# buttonboard-center.net
KiCad netlist of a schematic drawn in EAGLE
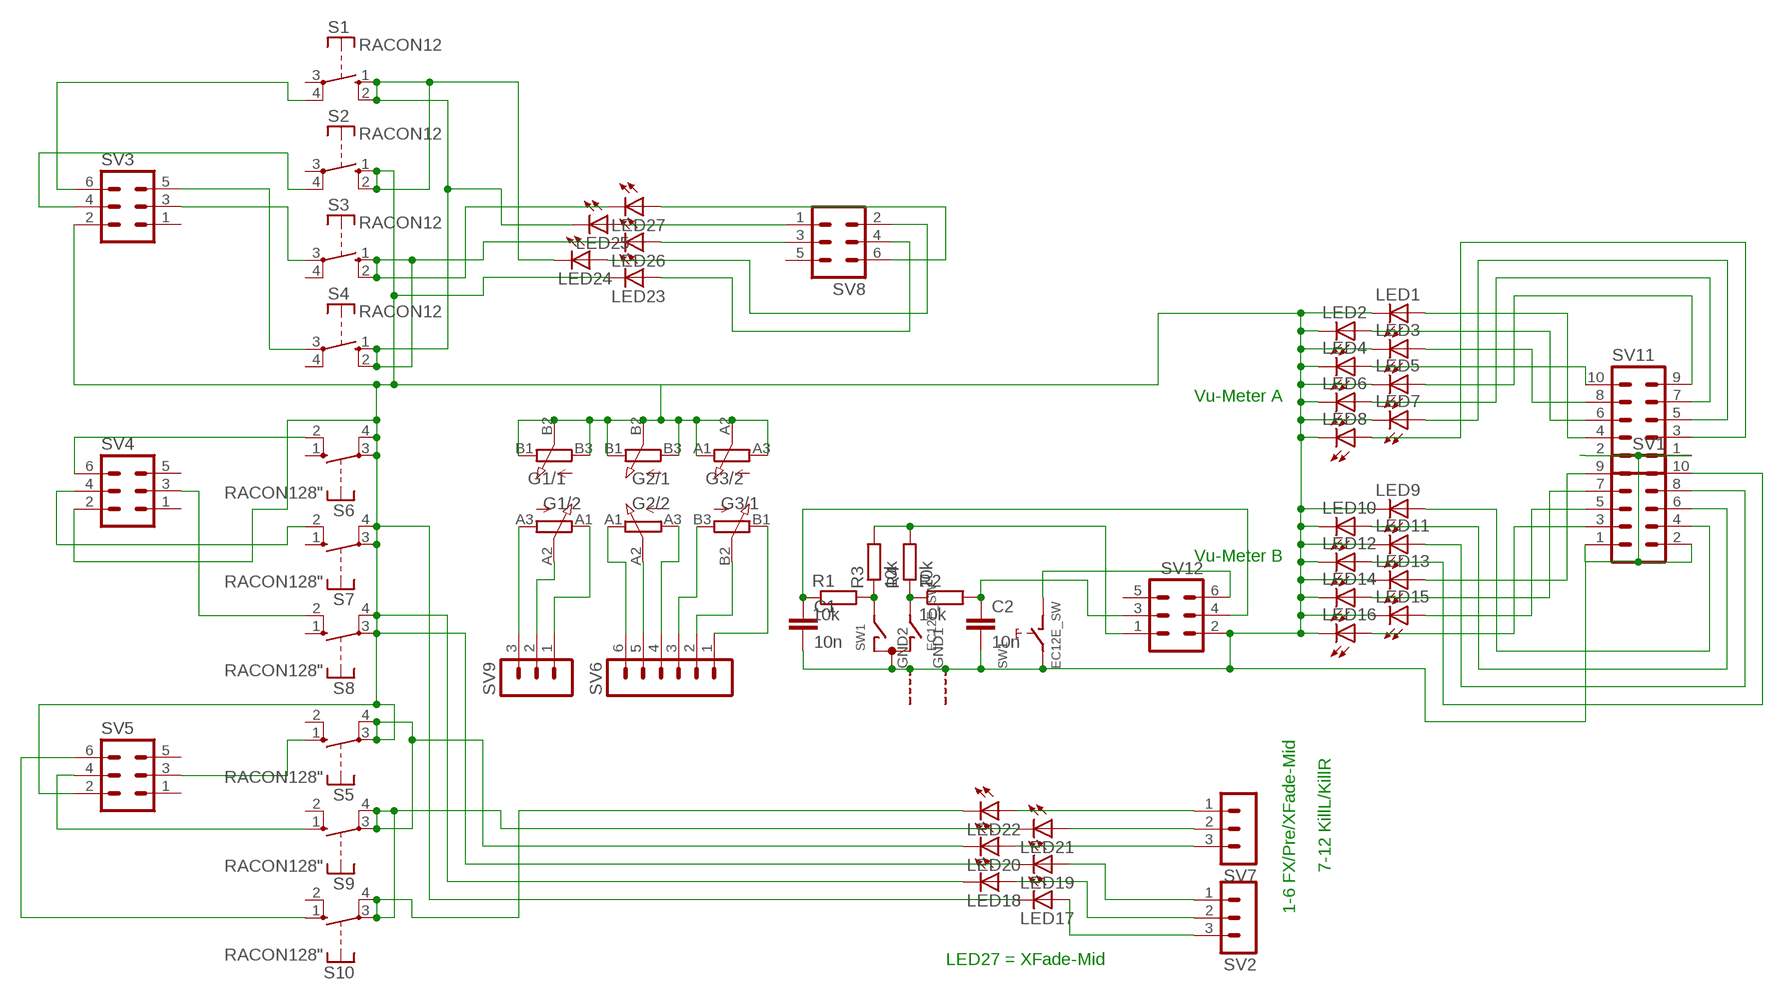
[diagram p0: schematic, sheet 1]

(export (version "E")
  (design (tool "Eeschema 10.0.6"))
  (components
    (comp (ref "C1")
      (value "10n")
      (footprint "eagle-import:C025-025X050")
      (libsource (lib "eagle-import") (part "C-EU025-025X050"))
    )
    (comp (ref "C2")
      (value "10n")
      (footprint "eagle-import:C025-025X050")
      (libsource (lib "eagle-import") (part "C-EU025-025X050"))
    )
    (comp (ref "G1")
      (value "RS60112RS")
      (footprint "eagle-import:RS60112")
      (libsource (lib "eagle-import") (part "RS60112RS"))
    )
    (comp (ref "G2")
      (value "RS60112RS")
      (footprint "eagle-import:RS60112")
      (libsource (lib "eagle-import") (part "RS60112RS"))
    )
    (comp (ref "G3")
      (value "RS60112RS")
      (footprint "eagle-import:RS60112")
      (libsource (lib "eagle-import") (part "RS60112RS"))
    )
    (comp (ref "LED1")
      (value "LED3MM")
      (footprint "eagle-import:LED3MM")
      (libsource (lib "eagle-import") (part "LED3MM"))
    )
    (comp (ref "LED2")
      (value "LED3MM")
      (footprint "eagle-import:LED3MM")
      (libsource (lib "eagle-import") (part "LED3MM"))
    )
    (comp (ref "LED3")
      (value "LED3MM")
      (footprint "eagle-import:LED3MM")
      (libsource (lib "eagle-import") (part "LED3MM"))
    )
    (comp (ref "LED4")
      (value "LED3MM")
      (footprint "eagle-import:LED3MM")
      (libsource (lib "eagle-import") (part "LED3MM"))
    )
    (comp (ref "LED5")
      (value "LED3MM")
      (footprint "eagle-import:LED3MM")
      (libsource (lib "eagle-import") (part "LED3MM"))
    )
    (comp (ref "LED6")
      (value "LED3MM")
      (footprint "eagle-import:LED3MM")
      (libsource (lib "eagle-import") (part "LED3MM"))
    )
    (comp (ref "LED7")
      (value "LED3MM")
      (footprint "eagle-import:LED3MM")
      (libsource (lib "eagle-import") (part "LED3MM"))
    )
    (comp (ref "LED8")
      (value "LED3MM")
      (footprint "eagle-import:LED3MM")
      (libsource (lib "eagle-import") (part "LED3MM"))
    )
    (comp (ref "LED9")
      (value "LED3MM")
      (footprint "eagle-import:LED3MM")
      (libsource (lib "eagle-import") (part "LED3MM"))
    )
    (comp (ref "LED10")
      (value "LED3MM")
      (footprint "eagle-import:LED3MM")
      (libsource (lib "eagle-import") (part "LED3MM"))
    )
    (comp (ref "LED11")
      (value "LED3MM")
      (footprint "eagle-import:LED3MM")
      (libsource (lib "eagle-import") (part "LED3MM"))
    )
    (comp (ref "LED12")
      (value "LED3MM")
      (footprint "eagle-import:LED3MM")
      (libsource (lib "eagle-import") (part "LED3MM"))
    )
    (comp (ref "LED13")
      (value "LED3MM")
      (footprint "eagle-import:LED3MM")
      (libsource (lib "eagle-import") (part "LED3MM"))
    )
    (comp (ref "LED14")
      (value "LED3MM")
      (footprint "eagle-import:LED3MM")
      (libsource (lib "eagle-import") (part "LED3MM"))
    )
    (comp (ref "LED15")
      (value "LED3MM")
      (footprint "eagle-import:LED3MM")
      (libsource (lib "eagle-import") (part "LED3MM"))
    )
    (comp (ref "LED16")
      (value "LED3MM")
      (footprint "eagle-import:LED3MM")
      (libsource (lib "eagle-import") (part "LED3MM"))
    )
    (comp (ref "LED17")
      (value "LED3MM")
      (footprint "eagle-import:LED3MM")
      (libsource (lib "eagle-import") (part "LED3MM"))
    )
    (comp (ref "LED18")
      (value "LED3MM")
      (footprint "eagle-import:LED3MM")
      (libsource (lib "eagle-import") (part "LED3MM"))
    )
    (comp (ref "LED19")
      (value "LED3MM")
      (footprint "eagle-import:LED3MM")
      (libsource (lib "eagle-import") (part "LED3MM"))
    )
    (comp (ref "LED20")
      (value "LED3MM")
      (footprint "eagle-import:LED3MM")
      (libsource (lib "eagle-import") (part "LED3MM"))
    )
    (comp (ref "LED21")
      (value "LED3MM")
      (footprint "eagle-import:LED3MM")
      (libsource (lib "eagle-import") (part "LED3MM"))
    )
    (comp (ref "LED22")
      (value "LED3MM")
      (footprint "eagle-import:LED3MM")
      (libsource (lib "eagle-import") (part "LED3MM"))
    )
    (comp (ref "LED23")
      (value "LED3MM")
      (footprint "eagle-import:LED3MM")
      (libsource (lib "eagle-import") (part "LED3MM"))
    )
    (comp (ref "LED24")
      (value "LED3MM")
      (footprint "eagle-import:LED3MM")
      (libsource (lib "eagle-import") (part "LED3MM"))
    )
    (comp (ref "LED25")
      (value "LED3MM")
      (footprint "eagle-import:LED3MM")
      (libsource (lib "eagle-import") (part "LED3MM"))
    )
    (comp (ref "LED26")
      (value "LED3MM")
      (footprint "eagle-import:LED3MM")
      (libsource (lib "eagle-import") (part "LED3MM"))
    )
    (comp (ref "LED27")
      (value "LED3MM")
      (footprint "eagle-import:LED3MM")
      (libsource (lib "eagle-import") (part "LED3MM"))
    )
    (comp (ref "R1")
      (value "10k")
      (footprint "eagle-import:0207_7")
      (libsource (lib "eagle-import") (part "R-EU_0207/7"))
    )
    (comp (ref "R2")
      (value "10k")
      (footprint "eagle-import:0207_7")
      (libsource (lib "eagle-import") (part "R-EU_0207/7"))
    )
    (comp (ref "R3")
      (value "10k")
      (footprint "eagle-import:0207_7")
      (libsource (lib "eagle-import") (part "R-EU_0207/7"))
    )
    (comp (ref "R4")
      (value "10k")
      (footprint "eagle-import:0207_7")
      (libsource (lib "eagle-import") (part "R-EU_0207/7"))
    )
    (comp (ref "S1")
      (value "RACON12")
      (footprint "eagle-import:RACON12")
      (libsource (lib "eagle-import") (part "RACON12"))
    )
    (comp (ref "S2")
      (value "RACON12")
      (footprint "eagle-import:RACON12")
      (libsource (lib "eagle-import") (part "RACON12"))
    )
    (comp (ref "S3")
      (value "RACON12")
      (footprint "eagle-import:RACON12")
      (libsource (lib "eagle-import") (part "RACON12"))
    )
    (comp (ref "S4")
      (value "RACON12")
      (footprint "eagle-import:RACON12")
      (libsource (lib "eagle-import") (part "RACON12"))
    )
    (comp (ref "S5")
      (value "RACON128\"")
      (footprint "eagle-import:RACON8")
      (libsource (lib "eagle-import") (part "RACON128{dblquote}"))
    )
    (comp (ref "S6")
      (value "RACON128\"")
      (footprint "eagle-import:RACON8")
      (libsource (lib "eagle-import") (part "RACON128{dblquote}"))
    )
    (comp (ref "S7")
      (value "RACON128\"")
      (footprint "eagle-import:RACON8")
      (libsource (lib "eagle-import") (part "RACON128{dblquote}"))
    )
    (comp (ref "S8")
      (value "RACON128\"")
      (footprint "eagle-import:RACON8")
      (libsource (lib "eagle-import") (part "RACON128{dblquote}"))
    )
    (comp (ref "S9")
      (value "RACON128\"")
      (footprint "eagle-import:RACON8")
      (libsource (lib "eagle-import") (part "RACON128{dblquote}"))
    )
    (comp (ref "S10")
      (value "RACON128\"")
      (footprint "eagle-import:RACON8")
      (libsource (lib "eagle-import") (part "RACON128{dblquote}"))
    )
    (comp (ref "SV1")
      (value "MA05-2")
      (footprint "eagle-import:MA05-2")
      (fields (field (name "OC_FARNELL") "unknown") (field (name "OC_NEWARK") "unknown"))
      (libsource (lib "eagle-import") (part "MA05-2"))
    )
    (comp (ref "SV2")
      (value "MA03-1")
      (footprint "eagle-import:MA03-1")
      (libsource (lib "eagle-import") (part "MA03-1"))
    )
    (comp (ref "SV3")
      (value "MA03-2")
      (footprint "eagle-import:MA03-2")
      (libsource (lib "eagle-import") (part "MA03-2"))
    )
    (comp (ref "SV4")
      (value "MA03-2")
      (footprint "eagle-import:MA03-2")
      (libsource (lib "eagle-import") (part "MA03-2"))
    )
    (comp (ref "SV5")
      (value "MA03-2")
      (footprint "eagle-import:MA03-2")
      (libsource (lib "eagle-import") (part "MA03-2"))
    )
    (comp (ref "SV6")
      (value "MA06-1")
      (footprint "eagle-import:MA06-1")
      (libsource (lib "eagle-import") (part "MA06-1"))
    )
    (comp (ref "SV7")
      (value "MA03-1")
      (footprint "eagle-import:MA03-1")
      (libsource (lib "eagle-import") (part "MA03-1"))
    )
    (comp (ref "SV8")
      (value "MA03-2")
      (footprint "eagle-import:MA03-2")
      (libsource (lib "eagle-import") (part "MA03-2"))
    )
    (comp (ref "SV9")
      (value "MA03-1")
      (footprint "eagle-import:MA03-1")
      (libsource (lib "eagle-import") (part "MA03-1"))
    )
    (comp (ref "SV11")
      (value "MA05-2")
      (footprint "eagle-import:MA05-2")
      (libsource (lib "eagle-import") (part "MA05-2"))
    )
    (comp (ref "SV12")
      (value "MA03-2")
      (footprint "eagle-import:MA03-2")
      (fields (field (name "OC_FARNELL") "unknown") (field (name "OC_NEWARK") "unknown"))
      (libsource (lib "eagle-import") (part "MA03-2"))
    )
    (comp (ref "SW1")
      (value "EC12E_SW")
      (footprint "eagle-import:ALPS_EC12E_SW")
      (fields (field (name "MPN") "EC12E2424407"))
      (libsource (lib "eagle-import") (part "EC12E_SW"))
    )
  )
  (nets
    (net (code "1") (name "Net-(C1-Pad1)") (class "Default")
      (node (ref "C1") (pin "1") (pinfunction "1_1") (pintype "passive"))
      (node (ref "R1") (pin "1") (pinfunction "1_1") (pintype "passive"))
      (node (ref "SV12") (pin "4") (pinfunction "4_4") (pintype "passive"))
    )
    (net (code "2") (name "Net-(C2-Pad1)") (class "Default")
      (node (ref "C2") (pin "1") (pinfunction "1_1") (pintype "passive"))
      (node (ref "R2") (pin "2") (pinfunction "2_2") (pintype "passive"))
      (node (ref "SV12") (pin "3") (pinfunction "3_3") (pintype "passive"))
    )
    (net (code "3") (name "Net-(G1A-A)") (class "Default")
      (node (ref "G1") (pin "A3") (pinfunction "A_A3") (pintype "passive"))
      (node (ref "SV9") (pin "3") (pinfunction "3_3") (pintype "passive"))
    )
    (net (code "4") (name "Net-(G1A-E)") (class "Default")
      (node (ref "G1") (pin "A1") (pinfunction "E_A1") (pintype "passive"))
      (node (ref "SV9") (pin "1") (pinfunction "1_1") (pintype "passive"))
    )
    (net (code "5") (name "Net-(G1A-S)") (class "Default")
      (node (ref "G1") (pin "A2") (pinfunction "S_A2") (pintype "passive"))
      (node (ref "SV9") (pin "2") (pinfunction "2_2") (pintype "passive"))
    )
    (net (code "6") (name "Net-(G1B-A)") (class "Default")
      (node (ref "C1") (pin "2") (pinfunction "2_2") (pintype "passive"))
      (node (ref "C2") (pin "2") (pinfunction "2_2") (pintype "passive"))
      (node (ref "G1") (pin "B1") (pinfunction "E_B1") (pintype "passive"))
      (node (ref "G1") (pin "B2") (pinfunction "S_B2") (pintype "passive"))
      (node (ref "G1") (pin "B3") (pinfunction "A_B3") (pintype "passive"))
      (node (ref "G2") (pin "B1") (pinfunction "E_B1") (pintype "passive"))
      (node (ref "G2") (pin "B2") (pinfunction "S_B2") (pintype "passive"))
      (node (ref "G2") (pin "B3") (pinfunction "A_B3") (pintype "passive"))
      (node (ref "G3") (pin "A1") (pinfunction "E_A1") (pintype "passive"))
      (node (ref "G3") (pin "A2") (pinfunction "S_A2") (pintype "passive"))
      (node (ref "G3") (pin "A3") (pinfunction "A_A3") (pintype "passive"))
      (node (ref "LED1") (pin "K") (pinfunction "C_K") (pintype "passive"))
      (node (ref "LED10") (pin "K") (pinfunction "C_K") (pintype "passive"))
      (node (ref "LED11") (pin "K") (pinfunction "C_K") (pintype "passive"))
      (node (ref "LED12") (pin "K") (pinfunction "C_K") (pintype "passive"))
      (node (ref "LED13") (pin "K") (pinfunction "C_K") (pintype "passive"))
      (node (ref "LED14") (pin "K") (pinfunction "C_K") (pintype "passive"))
      (node (ref "LED15") (pin "K") (pinfunction "C_K") (pintype "passive"))
      (node (ref "LED16") (pin "K") (pinfunction "C_K") (pintype "passive"))
      (node (ref "LED17") (pin "K") (pinfunction "C_K") (pintype "passive"))
      (node (ref "LED18") (pin "K") (pinfunction "C_K") (pintype "passive"))
      (node (ref "LED19") (pin "K") (pinfunction "C_K") (pintype "passive"))
      (node (ref "LED2") (pin "K") (pinfunction "C_K") (pintype "passive"))
      (node (ref "LED20") (pin "K") (pinfunction "C_K") (pintype "passive"))
      (node (ref "LED21") (pin "K") (pinfunction "C_K") (pintype "passive"))
      (node (ref "LED22") (pin "K") (pinfunction "C_K") (pintype "passive"))
      (node (ref "LED23") (pin "K") (pinfunction "C_K") (pintype "passive"))
      (node (ref "LED24") (pin "K") (pinfunction "C_K") (pintype "passive"))
      (node (ref "LED25") (pin "K") (pinfunction "C_K") (pintype "passive"))
      (node (ref "LED26") (pin "K") (pinfunction "C_K") (pintype "passive"))
      (node (ref "LED27") (pin "K") (pinfunction "C_K") (pintype "passive"))
      (node (ref "LED3") (pin "K") (pinfunction "C_K") (pintype "passive"))
      (node (ref "LED4") (pin "K") (pinfunction "C_K") (pintype "passive"))
      (node (ref "LED5") (pin "K") (pinfunction "C_K") (pintype "passive"))
      (node (ref "LED6") (pin "K") (pinfunction "C_K") (pintype "passive"))
      (node (ref "LED7") (pin "K") (pinfunction "C_K") (pintype "passive"))
      (node (ref "LED8") (pin "K") (pinfunction "C_K") (pintype "passive"))
      (node (ref "LED9") (pin "K") (pinfunction "C_K") (pintype "passive"))
      (node (ref "S1") (pin "1") (pinfunction "S_1") (pintype "passive"))
      (node (ref "S1") (pin "2") (pinfunction "S_2") (pintype "passive"))
      (node (ref "S10") (pin "3") (pinfunction "P_3") (pintype "passive"))
      (node (ref "S10") (pin "4") (pinfunction "P_4") (pintype "passive"))
      (node (ref "S2") (pin "1") (pinfunction "S_1") (pintype "passive"))
      (node (ref "S2") (pin "2") (pinfunction "S_2") (pintype "passive"))
      (node (ref "S3") (pin "1") (pinfunction "S_1") (pintype "passive"))
      (node (ref "S3") (pin "2") (pinfunction "S_2") (pintype "passive"))
      (node (ref "S4") (pin "1") (pinfunction "S_1") (pintype "passive"))
      (node (ref "S4") (pin "2") (pinfunction "S_2") (pintype "passive"))
      (node (ref "S5") (pin "3") (pinfunction "P_3") (pintype "passive"))
      (node (ref "S5") (pin "4") (pinfunction "P_4") (pintype "passive"))
      (node (ref "S6") (pin "3") (pinfunction "P_3") (pintype "passive"))
      (node (ref "S6") (pin "4") (pinfunction "P_4") (pintype "passive"))
      (node (ref "S7") (pin "3") (pinfunction "P_3") (pintype "passive"))
      (node (ref "S7") (pin "4") (pinfunction "P_4") (pintype "passive"))
      (node (ref "S8") (pin "3") (pinfunction "P_3") (pintype "passive"))
      (node (ref "S8") (pin "4") (pinfunction "P_4") (pintype "passive"))
      (node (ref "S9") (pin "3") (pinfunction "P_3") (pintype "passive"))
      (node (ref "S9") (pin "4") (pinfunction "P_4") (pintype "passive"))
      (node (ref "SV1") (pin "1") (pinfunction "1_1") (pintype "passive"))
      (node (ref "SV1") (pin "2") (pinfunction "2_2") (pintype "passive"))
      (node (ref "SV11") (pin "1") (pinfunction "1_1") (pintype "passive"))
      (node (ref "SV11") (pin "2") (pinfunction "2_2") (pintype "passive"))
      (node (ref "SV12") (pin "2") (pinfunction "2_2") (pintype "passive"))
      (node (ref "SV3") (pin "2") (pinfunction "2_2") (pintype "passive"))
      (node (ref "SV4") (pin "2") (pinfunction "2_2") (pintype "passive"))
      (node (ref "SV5") (pin "2") (pinfunction "2_2") (pintype "passive"))
      (node (ref "SW1") (pin "C") (pinfunction "C_C") (pintype "passive"))
      (node (ref "SW1") (pin "E") (pinfunction "2_E") (pintype "passive"))
      (node (ref "SW1") (pin "GND1") (pinfunction "G_GND1") (pintype "passive"))
      (node (ref "SW1") (pin "GND2") (pinfunction "G_GND2") (pintype "passive"))
    )
    (net (code "7") (name "Net-(G2A-A)") (class "Default")
      (node (ref "G2") (pin "A3") (pinfunction "A_A3") (pintype "passive"))
      (node (ref "SV6") (pin "4") (pinfunction "4_4") (pintype "passive"))
    )
    (net (code "8") (name "Net-(G2A-E)") (class "Default")
      (node (ref "G2") (pin "A1") (pinfunction "E_A1") (pintype "passive"))
      (node (ref "SV6") (pin "6") (pinfunction "6_6") (pintype "passive"))
    )
    (net (code "9") (name "Net-(G2A-S)") (class "Default")
      (node (ref "G2") (pin "A2") (pinfunction "S_A2") (pintype "passive"))
      (node (ref "SV6") (pin "5") (pinfunction "5_5") (pintype "passive"))
    )
    (net (code "10") (name "Net-(G3B-A)") (class "Default")
      (node (ref "G3") (pin "B3") (pinfunction "A_B3") (pintype "passive"))
      (node (ref "SV6") (pin "3") (pinfunction "3_3") (pintype "passive"))
    )
    (net (code "11") (name "Net-(G3B-E)") (class "Default")
      (node (ref "G3") (pin "B1") (pinfunction "E_B1") (pintype "passive"))
      (node (ref "SV6") (pin "1") (pinfunction "1_1") (pintype "passive"))
    )
    (net (code "12") (name "Net-(G3B-S)") (class "Default")
      (node (ref "G3") (pin "B2") (pinfunction "S_B2") (pintype "passive"))
      (node (ref "SV6") (pin "2") (pinfunction "2_2") (pintype "passive"))
    )
    (net (code "13") (name "Net-(LED1-PadA)") (class "Default")
      (node (ref "LED1") (pin "A") (pinfunction "A_A") (pintype "passive"))
      (node (ref "SV11") (pin "4") (pinfunction "4_4") (pintype "passive"))
    )
    (net (code "14") (name "Net-(LED2-PadA)") (class "Default")
      (node (ref "LED2") (pin "A") (pinfunction "A_A") (pintype "passive"))
      (node (ref "SV11") (pin "6") (pinfunction "6_6") (pintype "passive"))
    )
    (net (code "15") (name "Net-(LED3-PadA)") (class "Default")
      (node (ref "LED3") (pin "A") (pinfunction "A_A") (pintype "passive"))
      (node (ref "SV11") (pin "8") (pinfunction "8_8") (pintype "passive"))
    )
    (net (code "16") (name "Net-(LED4-PadA)") (class "Default")
      (node (ref "LED4") (pin "A") (pinfunction "A_A") (pintype "passive"))
      (node (ref "SV11") (pin "10") (pinfunction "10_10") (pintype "passive"))
    )
    (net (code "17") (name "Net-(LED5-PadA)") (class "Default")
      (node (ref "LED5") (pin "A") (pinfunction "A_A") (pintype "passive"))
      (node (ref "SV11") (pin "9") (pinfunction "9_9") (pintype "passive"))
    )
    (net (code "18") (name "Net-(LED6-PadA)") (class "Default")
      (node (ref "LED6") (pin "A") (pinfunction "A_A") (pintype "passive"))
      (node (ref "SV11") (pin "7") (pinfunction "7_7") (pintype "passive"))
    )
    (net (code "19") (name "Net-(LED7-PadA)") (class "Default")
      (node (ref "LED7") (pin "A") (pinfunction "A_A") (pintype "passive"))
      (node (ref "SV11") (pin "5") (pinfunction "5_5") (pintype "passive"))
    )
    (net (code "20") (name "Net-(LED8-PadA)") (class "Default")
      (node (ref "LED8") (pin "A") (pinfunction "A_A") (pintype "passive"))
      (node (ref "SV11") (pin "3") (pinfunction "3_3") (pintype "passive"))
    )
    (net (code "21") (name "Net-(LED9-PadA)") (class "Default")
      (node (ref "LED9") (pin "A") (pinfunction "A_A") (pintype "passive"))
      (node (ref "SV1") (pin "4") (pinfunction "4_4") (pintype "passive"))
    )
    (net (code "22") (name "Net-(LED10-PadA)") (class "Default")
      (node (ref "LED10") (pin "A") (pinfunction "A_A") (pintype "passive"))
      (node (ref "SV1") (pin "6") (pinfunction "6_6") (pintype "passive"))
    )
    (net (code "23") (name "Net-(LED11-PadA)") (class "Default")
      (node (ref "LED11") (pin "A") (pinfunction "A_A") (pintype "passive"))
      (node (ref "SV1") (pin "8") (pinfunction "8_8") (pintype "passive"))
    )
    (net (code "24") (name "Net-(LED12-PadA)") (class "Default")
      (node (ref "LED12") (pin "A") (pinfunction "A_A") (pintype "passive"))
      (node (ref "SV1") (pin "10") (pinfunction "10_10") (pintype "passive"))
    )
    (net (code "25") (name "Net-(LED13-PadA)") (class "Default")
      (node (ref "LED13") (pin "A") (pinfunction "A_A") (pintype "passive"))
      (node (ref "SV1") (pin "9") (pinfunction "9_9") (pintype "passive"))
    )
    (net (code "26") (name "Net-(LED14-PadA)") (class "Default")
      (node (ref "LED14") (pin "A") (pinfunction "A_A") (pintype "passive"))
      (node (ref "SV1") (pin "7") (pinfunction "7_7") (pintype "passive"))
    )
    (net (code "27") (name "Net-(LED15-PadA)") (class "Default")
      (node (ref "LED15") (pin "A") (pinfunction "A_A") (pintype "passive"))
      (node (ref "SV1") (pin "5") (pinfunction "5_5") (pintype "passive"))
    )
    (net (code "28") (name "Net-(LED16-PadA)") (class "Default")
      (node (ref "LED16") (pin "A") (pinfunction "A_A") (pintype "passive"))
      (node (ref "SV1") (pin "3") (pinfunction "3_3") (pintype "passive"))
    )
    (net (code "29") (name "Net-(LED17-PadA)") (class "Default")
      (node (ref "LED17") (pin "A") (pinfunction "A_A") (pintype "passive"))
      (node (ref "SV2") (pin "3") (pinfunction "3_3") (pintype "passive"))
    )
    (net (code "30") (name "Net-(LED18-PadA)") (class "Default")
      (node (ref "LED18") (pin "A") (pinfunction "A_A") (pintype "passive"))
      (node (ref "SV2") (pin "2") (pinfunction "2_2") (pintype "passive"))
    )
    (net (code "31") (name "Net-(LED19-PadA)") (class "Default")
      (node (ref "LED19") (pin "A") (pinfunction "A_A") (pintype "passive"))
      (node (ref "SV2") (pin "1") (pinfunction "1_1") (pintype "passive"))
    )
    (net (code "32") (name "Net-(LED20-PadA)") (class "Default")
      (node (ref "LED20") (pin "A") (pinfunction "A_A") (pintype "passive"))
      (node (ref "SV7") (pin "3") (pinfunction "3_3") (pintype "passive"))
    )
    (net (code "33") (name "Net-(LED21-PadA)") (class "Default")
      (node (ref "LED21") (pin "A") (pinfunction "A_A") (pintype "passive"))
      (node (ref "SV7") (pin "2") (pinfunction "2_2") (pintype "passive"))
    )
    (net (code "34") (name "Net-(LED22-PadA)") (class "Default")
      (node (ref "LED22") (pin "A") (pinfunction "A_A") (pintype "passive"))
      (node (ref "SV7") (pin "1") (pinfunction "1_1") (pintype "passive"))
    )
    (net (code "35") (name "Net-(LED23-PadA)") (class "Default")
      (node (ref "LED23") (pin "A") (pinfunction "A_A") (pintype "passive"))
      (node (ref "SV8") (pin "4") (pinfunction "4_4") (pintype "passive"))
    )
    (net (code "36") (name "Net-(LED24-PadA)") (class "Default")
      (node (ref "LED24") (pin "A") (pinfunction "A_A") (pintype "passive"))
      (node (ref "SV8") (pin "2") (pinfunction "2_2") (pintype "passive"))
    )
    (net (code "37") (name "Net-(LED25-PadA)") (class "Default")
      (node (ref "LED25") (pin "A") (pinfunction "A_A") (pintype "passive"))
      (node (ref "SV8") (pin "1") (pinfunction "1_1") (pintype "passive"))
    )
    (net (code "38") (name "Net-(LED26-PadA)") (class "Default")
      (node (ref "LED26") (pin "A") (pinfunction "A_A") (pintype "passive"))
      (node (ref "SV8") (pin "3") (pinfunction "3_3") (pintype "passive"))
    )
    (net (code "39") (name "Net-(LED27-PadA)") (class "Default")
      (node (ref "LED27") (pin "A") (pinfunction "A_A") (pintype "passive"))
      (node (ref "SV8") (pin "6") (pinfunction "6_6") (pintype "passive"))
    )
    (net (code "40") (name "Net-(R1-Pad2)") (class "Default")
      (node (ref "R1") (pin "2") (pinfunction "2_2") (pintype "passive"))
      (node (ref "R3") (pin "1") (pinfunction "1_1") (pintype "passive"))
      (node (ref "SW1") (pin "A") (pinfunction "A_A") (pintype "passive"))
    )
    (net (code "41") (name "Net-(R2-Pad1)") (class "Default")
      (node (ref "R2") (pin "1") (pinfunction "1_1") (pintype "passive"))
      (node (ref "R4") (pin "1") (pinfunction "1_1") (pintype "passive"))
      (node (ref "SW1") (pin "B") (pinfunction "B_B") (pintype "passive"))
    )
    (net (code "42") (name "Net-(R3-Pad2)") (class "Default")
      (node (ref "R3") (pin "2") (pinfunction "2_2") (pintype "passive"))
      (node (ref "R4") (pin "2") (pinfunction "2_2") (pintype "passive"))
      (node (ref "SV12") (pin "1") (pinfunction "1_1") (pintype "passive"))
    )
    (net (code "43") (name "Net-(S1-P-Pad4)") (class "Default")
      (node (ref "S1") (pin "4") (pinfunction "P_4") (pintype "passive"))
      (node (ref "SV3") (pin "6") (pinfunction "6_6") (pintype "passive"))
    )
    (net (code "44") (name "Net-(S2-P-Pad4)") (class "Default")
      (node (ref "S2") (pin "4") (pinfunction "P_4") (pintype "passive"))
      (node (ref "SV3") (pin "4") (pinfunction "4_4") (pintype "passive"))
    )
    (net (code "45") (name "Net-(S3-P-Pad3)") (class "Default")
      (node (ref "S3") (pin "3") (pinfunction "P_3") (pintype "passive"))
      (node (ref "SV3") (pin "3") (pinfunction "3_3") (pintype "passive"))
    )
    (net (code "46") (name "Net-(S4-P-Pad3)") (class "Default")
      (node (ref "S4") (pin "3") (pinfunction "P_3") (pintype "passive"))
      (node (ref "SV3") (pin "5") (pinfunction "5_5") (pintype "passive"))
    )
    (net (code "47") (name "Net-(S5-S-Pad1)") (class "Default")
      (node (ref "S5") (pin "1") (pinfunction "S_1") (pintype "passive"))
      (node (ref "SV5") (pin "3") (pinfunction "3_3") (pintype "passive"))
    )
    (net (code "48") (name "Net-(S6-S-Pad2)") (class "Default")
      (node (ref "S6") (pin "2") (pinfunction "S_2") (pintype "passive"))
      (node (ref "SV4") (pin "6") (pinfunction "6_6") (pintype "passive"))
    )
    (net (code "49") (name "Net-(S7-S-Pad2)") (class "Default")
      (node (ref "S7") (pin "2") (pinfunction "S_2") (pintype "passive"))
      (node (ref "SV4") (pin "4") (pinfunction "4_4") (pintype "passive"))
    )
    (net (code "50") (name "Net-(S8-S-Pad2)") (class "Default")
      (node (ref "S8") (pin "2") (pinfunction "S_2") (pintype "passive"))
      (node (ref "SV4") (pin "3") (pinfunction "3_3") (pintype "passive"))
    )
    (net (code "51") (name "Net-(S9-S-Pad1)") (class "Default")
      (node (ref "S9") (pin "1") (pinfunction "S_1") (pintype "passive"))
      (node (ref "SV5") (pin "4") (pinfunction "4_4") (pintype "passive"))
    )
    (net (code "52") (name "Net-(S10-S-Pad1)") (class "Default")
      (node (ref "S10") (pin "1") (pinfunction "S_1") (pintype "passive"))
      (node (ref "SV5") (pin "6") (pinfunction "6_6") (pintype "passive"))
    )
    (net (code "53") (name "Net-(SW1B-1)") (class "Default")
      (node (ref "SV12") (pin "6") (pinfunction "6_6") (pintype "passive"))
      (node (ref "SW1") (pin "D") (pinfunction "1_D") (pintype "passive"))
    )
    (net (code "54") (name "unconnected-(S1-P-Pad3)") (class "Default")
      (node (ref "S1") (pin "3") (pinfunction "P_3") (pintype "passive"))
    )
    (net (code "55") (name "unconnected-(S2-P-Pad3)") (class "Default")
      (node (ref "S2") (pin "3") (pinfunction "P_3") (pintype "passive"))
    )
    (net (code "56") (name "unconnected-(S3-P-Pad4)") (class "Default")
      (node (ref "S3") (pin "4") (pinfunction "P_4") (pintype "passive"))
    )
    (net (code "57") (name "unconnected-(S4-P-Pad4)") (class "Default")
      (node (ref "S4") (pin "4") (pinfunction "P_4") (pintype "passive"))
    )
    (net (code "58") (name "unconnected-(S5-S-Pad2)") (class "Default")
      (node (ref "S5") (pin "2") (pinfunction "S_2") (pintype "passive"))
    )
    (net (code "59") (name "unconnected-(S6-S-Pad1)") (class "Default")
      (node (ref "S6") (pin "1") (pinfunction "S_1") (pintype "passive"))
    )
    (net (code "60") (name "unconnected-(S7-S-Pad1)") (class "Default")
      (node (ref "S7") (pin "1") (pinfunction "S_1") (pintype "passive"))
    )
    (net (code "61") (name "unconnected-(S8-S-Pad1)") (class "Default")
      (node (ref "S8") (pin "1") (pinfunction "S_1") (pintype "passive"))
    )
    (net (code "62") (name "unconnected-(S9-S-Pad2)") (class "Default")
      (node (ref "S9") (pin "2") (pinfunction "S_2") (pintype "passive"))
    )
    (net (code "63") (name "unconnected-(S10-S-Pad2)") (class "Default")
      (node (ref "S10") (pin "2") (pinfunction "S_2") (pintype "passive"))
    )
    (net (code "64") (name "unconnected-(SV3-Pad1)") (class "Default")
      (node (ref "SV3") (pin "1") (pinfunction "1_1") (pintype "passive"))
    )
    (net (code "65") (name "unconnected-(SV4-Pad1)") (class "Default")
      (node (ref "SV4") (pin "1") (pinfunction "1_1") (pintype "passive"))
    )
    (net (code "66") (name "unconnected-(SV4-Pad5)") (class "Default")
      (node (ref "SV4") (pin "5") (pinfunction "5_5") (pintype "passive"))
    )
    (net (code "67") (name "unconnected-(SV5-Pad1)") (class "Default")
      (node (ref "SV5") (pin "1") (pinfunction "1_1") (pintype "passive"))
    )
    (net (code "68") (name "unconnected-(SV5-Pad5)") (class "Default")
      (node (ref "SV5") (pin "5") (pinfunction "5_5") (pintype "passive"))
    )
    (net (code "69") (name "unconnected-(SV8-Pad5)") (class "Default")
      (node (ref "SV8") (pin "5") (pinfunction "5_5") (pintype "passive"))
    )
    (net (code "70") (name "unconnected-(SV12-Pad5)") (class "Default")
      (node (ref "SV12") (pin "5") (pinfunction "5_5") (pintype "passive"))
    )
  )
)
